# CONTROL_ROUTING_CROSSPOINTS.net
KiCad netlist of a schematic drawn in Altium Designer
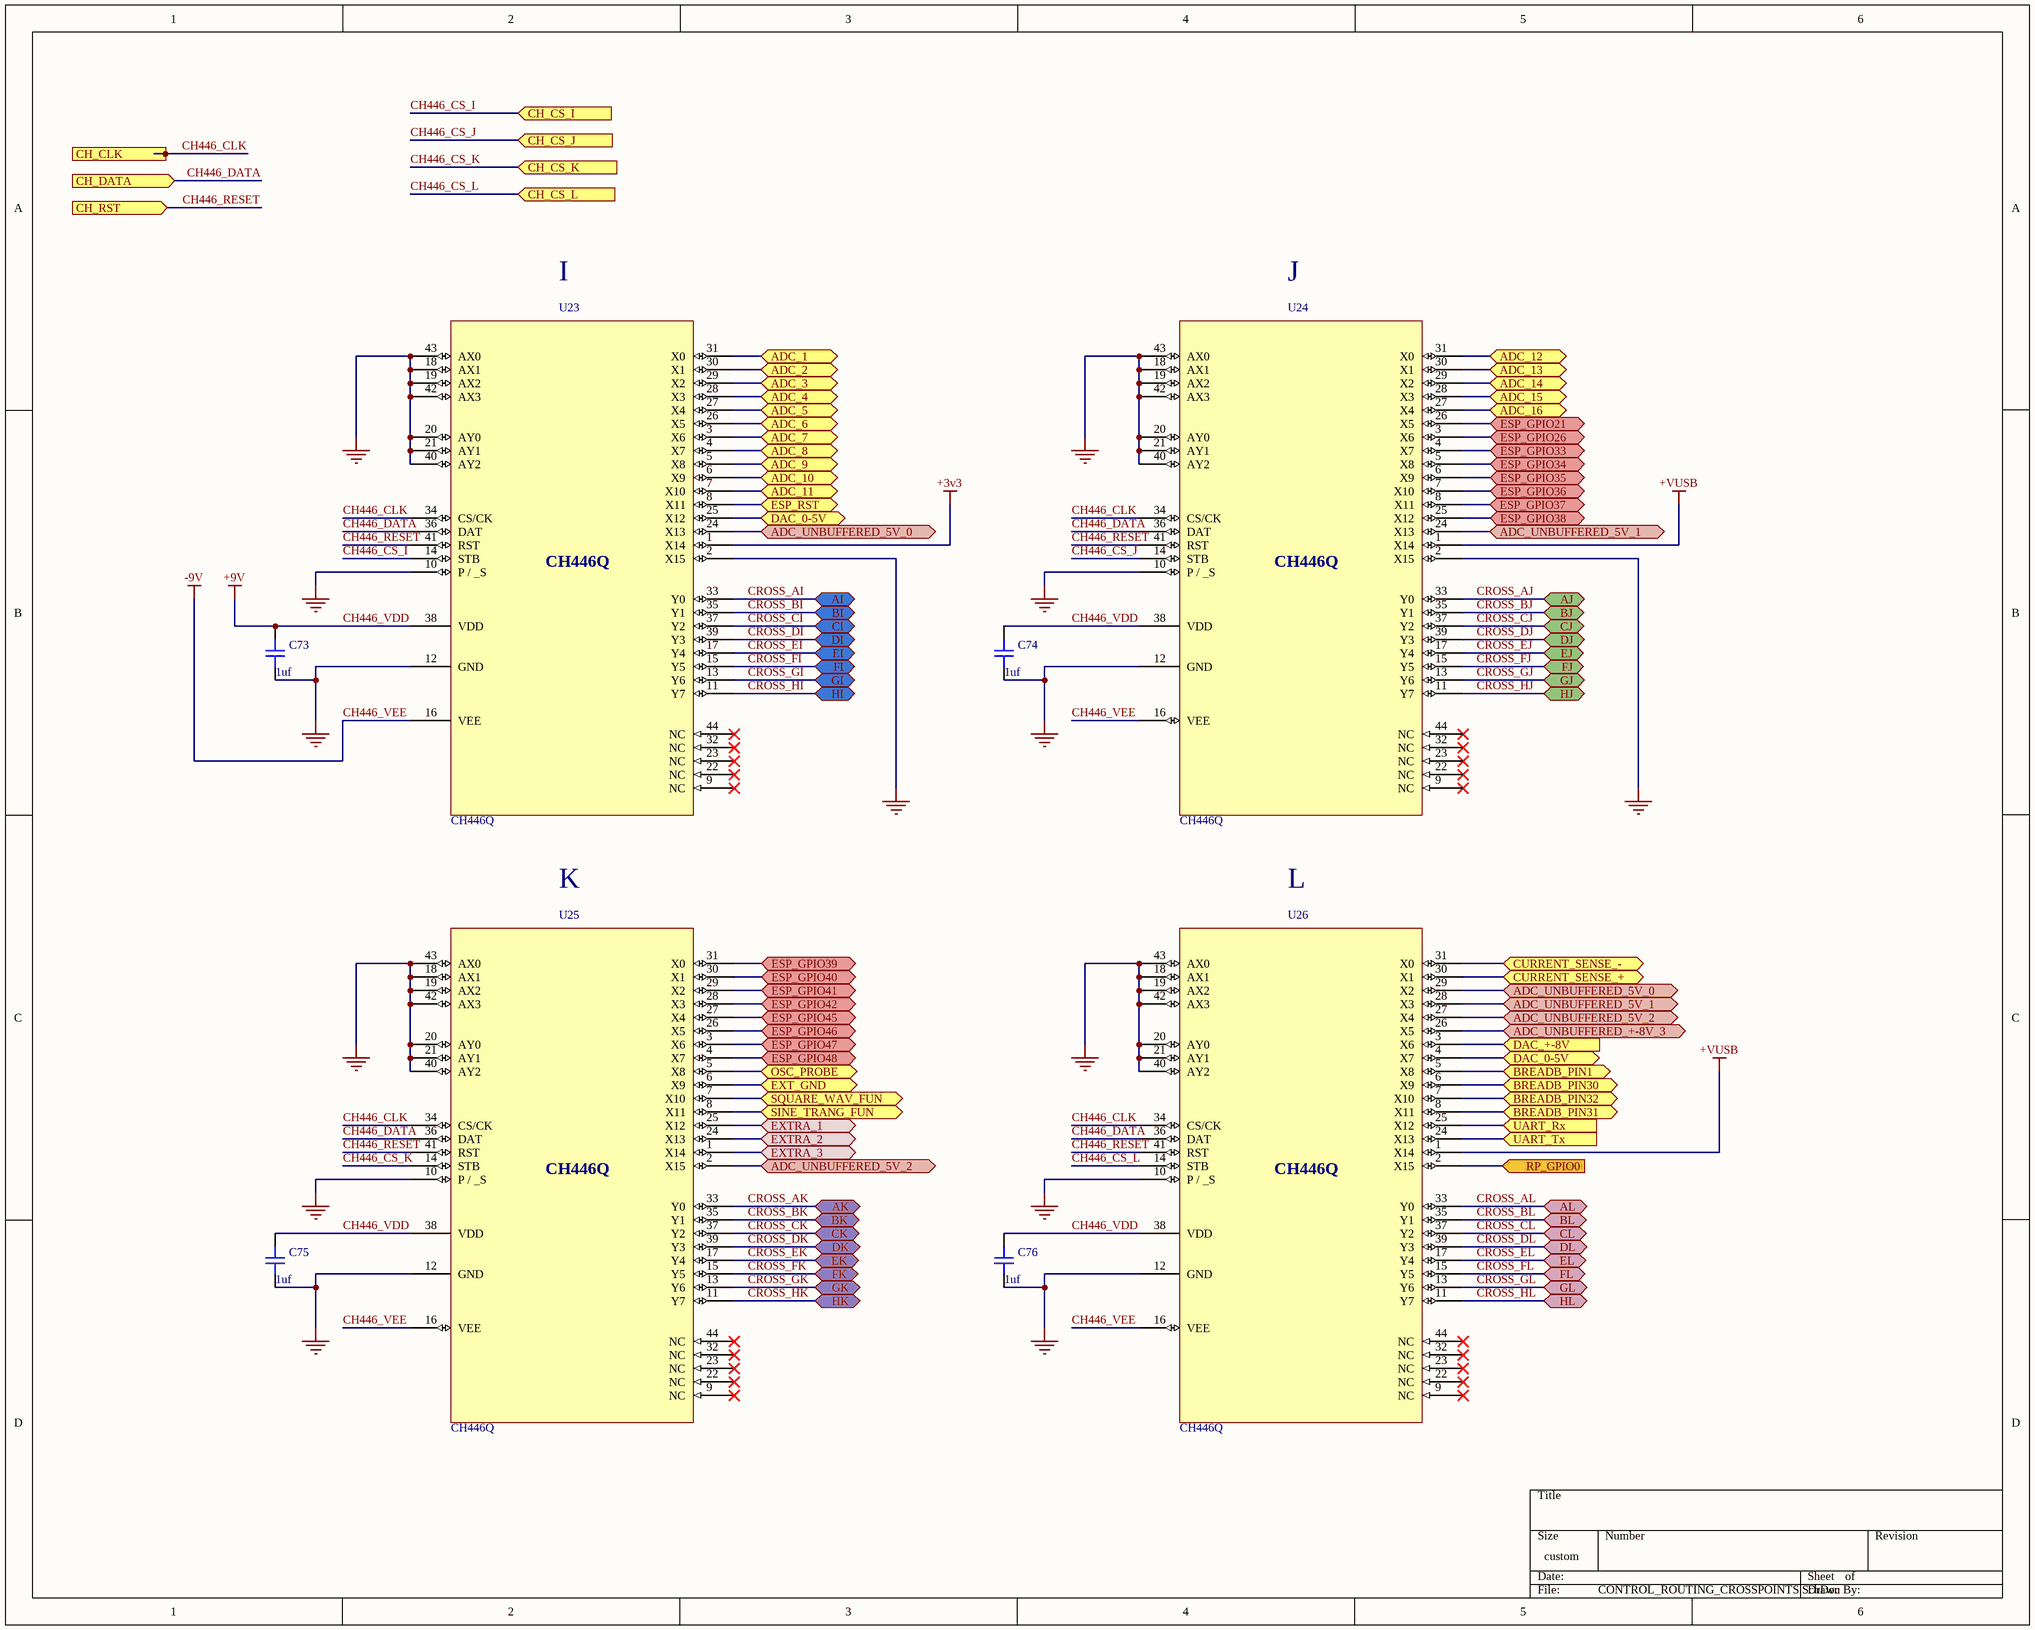
[diagram p0: CONTROL_ROUTING_CROSSPOINTS.SchDoc]

(export (version "E")
  (design (tool "Eeschema 10.0.6"))
  (components
    (comp (ref "C73")
      (value "1uf")
      (footprint "CAP_0603")
      (description "Capacitor SMD 0603")
      (libsource (lib "Schematic-Lib-PhilsLab") (part "CAP_0603"))
    )
    (comp (ref "C74")
      (value "1uf")
      (footprint "CAP_0603")
      (description "Capacitor SMD 0603")
      (libsource (lib "Schematic-Lib-PhilsLab") (part "CAP_0603"))
    )
    (comp (ref "C75")
      (value "1uf")
      (footprint "CAP_0603")
      (description "Capacitor SMD 0603")
      (libsource (lib "Schematic-Lib-PhilsLab") (part "CAP_0603"))
    )
    (comp (ref "C76")
      (value "1uf")
      (footprint "CAP_0603")
      (description "Capacitor SMD 0603")
      (libsource (lib "Schematic-Lib-PhilsLab") (part "CAP_0603"))
    )
    (comp (ref "U23") (value "CH446Q") (footprint "PG-LQFP-44") (libsource (lib "Schlib1") (part "CH446Q")))
    (comp (ref "U24") (value "CH446Q") (footprint "PG-LQFP-44") (libsource (lib "Schlib1") (part "CH446Q")))
    (comp (ref "U25") (value "CH446Q") (footprint "PG-LQFP-44") (libsource (lib "Schlib1") (part "CH446Q")))
    (comp (ref "U26") (value "CH446Q") (footprint "PG-LQFP-44") (libsource (lib "Schlib1") (part "CH446Q")))
  )
  (nets
    (net (code "1") (name "+3v3") (class "Default")
      (node (ref "U23") (pin "1") (pinfunction "X14_1") (pintype "bidirectional"))
    )
    (net (code "2") (name "+9V") (class "Default")
      (node (ref "C73") (pin "2") (pinfunction "2_2") (pintype "passive"))
      (node (ref "C74") (pin "2") (pinfunction "2_2") (pintype "passive"))
      (node (ref "C75") (pin "2") (pinfunction "2_2") (pintype "passive"))
      (node (ref "C76") (pin "2") (pinfunction "2_2") (pintype "passive"))
      (node (ref "U23") (pin "38") (pinfunction "VDD_38") (pintype "power_in"))
      (node (ref "U24") (pin "38") (pinfunction "VDD_38") (pintype "power_in"))
      (node (ref "U25") (pin "38") (pinfunction "VDD_38") (pintype "power_in"))
      (node (ref "U26") (pin "38") (pinfunction "VDD_38") (pintype "power_in"))
    )
    (net (code "3") (name "+VUSB") (class "Default")
      (node (ref "U24") (pin "1") (pinfunction "X14_1") (pintype "bidirectional"))
      (node (ref "U26") (pin "1") (pinfunction "X14_1") (pintype "bidirectional"))
    )
    (net (code "4") (name "-9V") (class "Default")
      (node (ref "U23") (pin "16") (pinfunction "VEE_16") (pintype "bidirectional"))
      (node (ref "U24") (pin "16") (pinfunction "VEE_16") (pintype "bidirectional"))
      (node (ref "U25") (pin "16") (pinfunction "VEE_16") (pintype "bidirectional"))
      (node (ref "U26") (pin "16") (pinfunction "VEE_16") (pintype "bidirectional"))
    )
    (net (code "5") (name "/ADC_1") (class "Default")
      (node (ref "U23") (pin "31") (pinfunction "X0_31") (pintype "bidirectional"))
    )
    (net (code "6") (name "/ADC_2") (class "Default")
      (node (ref "U23") (pin "30") (pinfunction "X1_30") (pintype "bidirectional"))
    )
    (net (code "7") (name "/ADC_3") (class "Default")
      (node (ref "U23") (pin "29") (pinfunction "X2_29") (pintype "bidirectional"))
    )
    (net (code "8") (name "/ADC_4") (class "Default")
      (node (ref "U23") (pin "28") (pinfunction "X3_28") (pintype "bidirectional"))
    )
    (net (code "9") (name "/ADC_5") (class "Default")
      (node (ref "U23") (pin "27") (pinfunction "X4_27") (pintype "bidirectional"))
    )
    (net (code "10") (name "/ADC_6") (class "Default")
      (node (ref "U23") (pin "26") (pinfunction "X5_26") (pintype "bidirectional"))
    )
    (net (code "11") (name "/ADC_7") (class "Default")
      (node (ref "U23") (pin "3") (pinfunction "X6_3") (pintype "bidirectional"))
    )
    (net (code "12") (name "/ADC_8") (class "Default")
      (node (ref "U23") (pin "4") (pinfunction "X7_4") (pintype "bidirectional"))
    )
    (net (code "13") (name "/ADC_9") (class "Default")
      (node (ref "U23") (pin "5") (pinfunction "X8_5") (pintype "bidirectional"))
    )
    (net (code "14") (name "/ADC_10") (class "Default")
      (node (ref "U23") (pin "6") (pinfunction "X9_6") (pintype "bidirectional"))
    )
    (net (code "15") (name "/ADC_11") (class "Default")
      (node (ref "U23") (pin "7") (pinfunction "X10_7") (pintype "bidirectional"))
    )
    (net (code "16") (name "/ADC_12") (class "Default")
      (node (ref "U24") (pin "31") (pinfunction "X0_31") (pintype "bidirectional"))
    )
    (net (code "17") (name "/ADC_13") (class "Default")
      (node (ref "U24") (pin "30") (pinfunction "X1_30") (pintype "bidirectional"))
    )
    (net (code "18") (name "/ADC_14") (class "Default")
      (node (ref "U24") (pin "29") (pinfunction "X2_29") (pintype "bidirectional"))
    )
    (net (code "19") (name "/ADC_15") (class "Default")
      (node (ref "U24") (pin "28") (pinfunction "X3_28") (pintype "bidirectional"))
    )
    (net (code "20") (name "/ADC_16") (class "Default")
      (node (ref "U24") (pin "27") (pinfunction "X4_27") (pintype "bidirectional"))
    )
    (net (code "21") (name "/ADC_UNBUFFERED_+-8V_3") (class "Default")
      (node (ref "U26") (pin "26") (pinfunction "X5_26") (pintype "bidirectional"))
    )
    (net (code "22") (name "/ADC_UNBUFFERED_5V_0") (class "Default")
      (node (ref "U23") (pin "24") (pinfunction "X13_24") (pintype "bidirectional"))
      (node (ref "U26") (pin "29") (pinfunction "X2_29") (pintype "bidirectional"))
    )
    (net (code "23") (name "/ADC_UNBUFFERED_5V_1") (class "Default")
      (node (ref "U24") (pin "24") (pinfunction "X13_24") (pintype "bidirectional"))
      (node (ref "U26") (pin "28") (pinfunction "X3_28") (pintype "bidirectional"))
    )
    (net (code "24") (name "/ADC_UNBUFFERED_5V_2") (class "Default")
      (node (ref "U25") (pin "2") (pinfunction "X15_2") (pintype "bidirectional"))
      (node (ref "U26") (pin "27") (pinfunction "X4_27") (pintype "bidirectional"))
    )
    (net (code "25") (name "/BREADB_PIN1") (class "Default")
      (node (ref "U26") (pin "5") (pinfunction "X8_5") (pintype "bidirectional"))
    )
    (net (code "26") (name "/BREADB_PIN30") (class "Default")
      (node (ref "U26") (pin "6") (pinfunction "X9_6") (pintype "bidirectional"))
    )
    (net (code "27") (name "/BREADB_PIN31") (class "Default")
      (node (ref "U26") (pin "8") (pinfunction "X11_8") (pintype "bidirectional"))
    )
    (net (code "28") (name "/BREADB_PIN32") (class "Default")
      (node (ref "U26") (pin "7") (pinfunction "X10_7") (pintype "bidirectional"))
    )
    (net (code "29") (name "/CH446_CLK") (class "Default")
      (node (ref "U23") (pin "34") (pinfunction "CS/CK_34") (pintype "bidirectional"))
      (node (ref "U24") (pin "34") (pinfunction "CS/CK_34") (pintype "bidirectional"))
      (node (ref "U25") (pin "34") (pinfunction "CS/CK_34") (pintype "bidirectional"))
      (node (ref "U26") (pin "34") (pinfunction "CS/CK_34") (pintype "bidirectional"))
    )
    (net (code "30") (name "/CH446_CS_I") (class "Default")
      (node (ref "U23") (pin "14") (pinfunction "STB_14") (pintype "bidirectional"))
    )
    (net (code "31") (name "/CH446_CS_J") (class "Default")
      (node (ref "U24") (pin "14") (pinfunction "STB_14") (pintype "bidirectional"))
    )
    (net (code "32") (name "/CH446_CS_K") (class "Default")
      (node (ref "U25") (pin "14") (pinfunction "STB_14") (pintype "bidirectional"))
    )
    (net (code "33") (name "/CH446_CS_L") (class "Default")
      (node (ref "U26") (pin "14") (pinfunction "STB_14") (pintype "bidirectional"))
    )
    (net (code "34") (name "/CH446_DATA") (class "Default")
      (node (ref "U23") (pin "36") (pinfunction "DAT_36") (pintype "bidirectional"))
      (node (ref "U24") (pin "36") (pinfunction "DAT_36") (pintype "bidirectional"))
      (node (ref "U25") (pin "36") (pinfunction "DAT_36") (pintype "bidirectional"))
      (node (ref "U26") (pin "36") (pinfunction "DAT_36") (pintype "bidirectional"))
    )
    (net (code "35") (name "/CH446_RESET") (class "Default")
      (node (ref "U23") (pin "41") (pinfunction "RST_41") (pintype "bidirectional"))
      (node (ref "U24") (pin "41") (pinfunction "RST_41") (pintype "bidirectional"))
      (node (ref "U25") (pin "41") (pinfunction "RST_41") (pintype "bidirectional"))
      (node (ref "U26") (pin "41") (pinfunction "RST_41") (pintype "bidirectional"))
    )
    (net (code "36") (name "/CROSS_AI") (class "Default")
      (node (ref "U23") (pin "33") (pinfunction "Y0_33") (pintype "bidirectional"))
    )
    (net (code "37") (name "/CROSS_AJ") (class "Default")
      (node (ref "U24") (pin "33") (pinfunction "Y0_33") (pintype "bidirectional"))
    )
    (net (code "38") (name "/CROSS_AK") (class "Default")
      (node (ref "U25") (pin "33") (pinfunction "Y0_33") (pintype "bidirectional"))
    )
    (net (code "39") (name "/CROSS_AL") (class "Default")
      (node (ref "U26") (pin "33") (pinfunction "Y0_33") (pintype "bidirectional"))
    )
    (net (code "40") (name "/CROSS_BI") (class "Default")
      (node (ref "U23") (pin "35") (pinfunction "Y1_35") (pintype "bidirectional"))
    )
    (net (code "41") (name "/CROSS_BJ") (class "Default")
      (node (ref "U24") (pin "35") (pinfunction "Y1_35") (pintype "bidirectional"))
    )
    (net (code "42") (name "/CROSS_BK") (class "Default")
      (node (ref "U25") (pin "35") (pinfunction "Y1_35") (pintype "bidirectional"))
    )
    (net (code "43") (name "/CROSS_BL") (class "Default")
      (node (ref "U26") (pin "35") (pinfunction "Y1_35") (pintype "bidirectional"))
    )
    (net (code "44") (name "/CROSS_CI") (class "Default")
      (node (ref "U23") (pin "37") (pinfunction "Y2_37") (pintype "bidirectional"))
    )
    (net (code "45") (name "/CROSS_CJ") (class "Default")
      (node (ref "U24") (pin "37") (pinfunction "Y2_37") (pintype "bidirectional"))
    )
    (net (code "46") (name "/CROSS_CK") (class "Default")
      (node (ref "U25") (pin "37") (pinfunction "Y2_37") (pintype "bidirectional"))
    )
    (net (code "47") (name "/CROSS_CL") (class "Default")
      (node (ref "U26") (pin "37") (pinfunction "Y2_37") (pintype "bidirectional"))
    )
    (net (code "48") (name "/CROSS_DI") (class "Default")
      (node (ref "U23") (pin "39") (pinfunction "Y3_39") (pintype "bidirectional"))
    )
    (net (code "49") (name "/CROSS_DJ") (class "Default")
      (node (ref "U24") (pin "39") (pinfunction "Y3_39") (pintype "bidirectional"))
    )
    (net (code "50") (name "/CROSS_DK") (class "Default")
      (node (ref "U25") (pin "39") (pinfunction "Y3_39") (pintype "bidirectional"))
    )
    (net (code "51") (name "/CROSS_DL") (class "Default")
      (node (ref "U26") (pin "39") (pinfunction "Y3_39") (pintype "bidirectional"))
    )
    (net (code "52") (name "/CROSS_EI") (class "Default")
      (node (ref "U23") (pin "17") (pinfunction "Y4_17") (pintype "bidirectional"))
    )
    (net (code "53") (name "/CROSS_EJ") (class "Default")
      (node (ref "U24") (pin "17") (pinfunction "Y4_17") (pintype "bidirectional"))
    )
    (net (code "54") (name "/CROSS_EK") (class "Default")
      (node (ref "U25") (pin "17") (pinfunction "Y4_17") (pintype "bidirectional"))
    )
    (net (code "55") (name "/CROSS_EL") (class "Default")
      (node (ref "U26") (pin "17") (pinfunction "Y4_17") (pintype "bidirectional"))
    )
    (net (code "56") (name "/CROSS_FI") (class "Default")
      (node (ref "U23") (pin "15") (pinfunction "Y5_15") (pintype "bidirectional"))
    )
    (net (code "57") (name "/CROSS_FJ") (class "Default")
      (node (ref "U24") (pin "15") (pinfunction "Y5_15") (pintype "bidirectional"))
    )
    (net (code "58") (name "/CROSS_FK") (class "Default")
      (node (ref "U25") (pin "15") (pinfunction "Y5_15") (pintype "bidirectional"))
    )
    (net (code "59") (name "/CROSS_FL") (class "Default")
      (node (ref "U26") (pin "15") (pinfunction "Y5_15") (pintype "bidirectional"))
    )
    (net (code "60") (name "/CROSS_GI") (class "Default")
      (node (ref "U23") (pin "13") (pinfunction "Y6_13") (pintype "bidirectional"))
    )
    (net (code "61") (name "/CROSS_GJ") (class "Default")
      (node (ref "U24") (pin "13") (pinfunction "Y6_13") (pintype "bidirectional"))
    )
    (net (code "62") (name "/CROSS_GK") (class "Default")
      (node (ref "U25") (pin "13") (pinfunction "Y6_13") (pintype "bidirectional"))
    )
    (net (code "63") (name "/CROSS_GL") (class "Default")
      (node (ref "U26") (pin "13") (pinfunction "Y6_13") (pintype "bidirectional"))
    )
    (net (code "64") (name "/CROSS_HI") (class "Default")
      (node (ref "U23") (pin "11") (pinfunction "Y7_11") (pintype "bidirectional"))
    )
    (net (code "65") (name "/CROSS_HJ") (class "Default")
      (node (ref "U24") (pin "11") (pinfunction "Y7_11") (pintype "bidirectional"))
    )
    (net (code "66") (name "/CROSS_HK") (class "Default")
      (node (ref "U25") (pin "11") (pinfunction "Y7_11") (pintype "bidirectional"))
    )
    (net (code "67") (name "/CROSS_HL") (class "Default")
      (node (ref "U26") (pin "11") (pinfunction "Y7_11") (pintype "bidirectional"))
    )
    (net (code "68") (name "/CURRENT_SENSE_+") (class "Default")
      (node (ref "U26") (pin "30") (pinfunction "X1_30") (pintype "bidirectional"))
    )
    (net (code "69") (name "/CURRENT_SENSE_-") (class "Default")
      (node (ref "U26") (pin "31") (pinfunction "X0_31") (pintype "bidirectional"))
    )
    (net (code "70") (name "/DAC_+-8V") (class "Default")
      (node (ref "U26") (pin "3") (pinfunction "X6_3") (pintype "bidirectional"))
    )
    (net (code "71") (name "/DAC_0-5V") (class "Default")
      (node (ref "U23") (pin "25") (pinfunction "X12_25") (pintype "bidirectional"))
      (node (ref "U26") (pin "4") (pinfunction "X7_4") (pintype "bidirectional"))
    )
    (net (code "72") (name "/ESP_GPIO21") (class "Default")
      (node (ref "U24") (pin "26") (pinfunction "X5_26") (pintype "bidirectional"))
    )
    (net (code "73") (name "/ESP_GPIO26") (class "Default")
      (node (ref "U24") (pin "3") (pinfunction "X6_3") (pintype "bidirectional"))
    )
    (net (code "74") (name "/ESP_GPIO33") (class "Default")
      (node (ref "U24") (pin "4") (pinfunction "X7_4") (pintype "bidirectional"))
    )
    (net (code "75") (name "/ESP_GPIO34") (class "Default")
      (node (ref "U24") (pin "5") (pinfunction "X8_5") (pintype "bidirectional"))
    )
    (net (code "76") (name "/ESP_GPIO35") (class "Default")
      (node (ref "U24") (pin "6") (pinfunction "X9_6") (pintype "bidirectional"))
    )
    (net (code "77") (name "/ESP_GPIO36") (class "Default")
      (node (ref "U24") (pin "7") (pinfunction "X10_7") (pintype "bidirectional"))
    )
    (net (code "78") (name "/ESP_GPIO37") (class "Default")
      (node (ref "U24") (pin "8") (pinfunction "X11_8") (pintype "bidirectional"))
    )
    (net (code "79") (name "/ESP_GPIO38") (class "Default")
      (node (ref "U24") (pin "25") (pinfunction "X12_25") (pintype "bidirectional"))
    )
    (net (code "80") (name "/ESP_GPIO39") (class "Default")
      (node (ref "U25") (pin "31") (pinfunction "X0_31") (pintype "bidirectional"))
    )
    (net (code "81") (name "/ESP_GPIO40") (class "Default")
      (node (ref "U25") (pin "30") (pinfunction "X1_30") (pintype "bidirectional"))
    )
    (net (code "82") (name "/ESP_GPIO41") (class "Default")
      (node (ref "U25") (pin "29") (pinfunction "X2_29") (pintype "bidirectional"))
    )
    (net (code "83") (name "/ESP_GPIO42") (class "Default")
      (node (ref "U25") (pin "28") (pinfunction "X3_28") (pintype "bidirectional"))
    )
    (net (code "84") (name "/ESP_GPIO45") (class "Default")
      (node (ref "U25") (pin "27") (pinfunction "X4_27") (pintype "bidirectional"))
    )
    (net (code "85") (name "/ESP_GPIO46") (class "Default")
      (node (ref "U25") (pin "26") (pinfunction "X5_26") (pintype "bidirectional"))
    )
    (net (code "86") (name "/ESP_GPIO47") (class "Default")
      (node (ref "U25") (pin "3") (pinfunction "X6_3") (pintype "bidirectional"))
    )
    (net (code "87") (name "/ESP_GPIO48") (class "Default")
      (node (ref "U25") (pin "4") (pinfunction "X7_4") (pintype "bidirectional"))
    )
    (net (code "88") (name "/ESP_RST") (class "Default")
      (node (ref "U23") (pin "8") (pinfunction "X11_8") (pintype "bidirectional"))
    )
    (net (code "89") (name "/EXTRA_1") (class "Default")
      (node (ref "U25") (pin "25") (pinfunction "X12_25") (pintype "bidirectional"))
    )
    (net (code "90") (name "/EXTRA_2") (class "Default")
      (node (ref "U25") (pin "24") (pinfunction "X13_24") (pintype "bidirectional"))
    )
    (net (code "91") (name "/EXTRA_3") (class "Default")
      (node (ref "U25") (pin "1") (pinfunction "X14_1") (pintype "bidirectional"))
    )
    (net (code "92") (name "/EXT_GND") (class "Default")
      (node (ref "U25") (pin "6") (pinfunction "X9_6") (pintype "bidirectional"))
    )
    (net (code "93") (name "/OSC_PROBE") (class "Default")
      (node (ref "U25") (pin "5") (pinfunction "X8_5") (pintype "bidirectional"))
    )
    (net (code "94") (name "/RP_GPIO0") (class "Default")
      (node (ref "U26") (pin "2") (pinfunction "X15_2") (pintype "bidirectional"))
    )
    (net (code "95") (name "/SINE_TRANG_FUN") (class "Default")
      (node (ref "U25") (pin "8") (pinfunction "X11_8") (pintype "bidirectional"))
    )
    (net (code "96") (name "/SQUARE_WAV_FUN") (class "Default")
      (node (ref "U25") (pin "7") (pinfunction "X10_7") (pintype "bidirectional"))
    )
    (net (code "97") (name "/UART_Rx") (class "Default")
      (node (ref "U26") (pin "25") (pinfunction "X12_25") (pintype "bidirectional"))
    )
    (net (code "98") (name "/UART_Tx") (class "Default")
      (node (ref "U26") (pin "24") (pinfunction "X13_24") (pintype "bidirectional"))
    )
    (net (code "99") (name "GND") (class "Default")
      (node (ref "C73") (pin "1") (pinfunction "1_1") (pintype "passive"))
      (node (ref "C74") (pin "1") (pinfunction "1_1") (pintype "passive"))
      (node (ref "C75") (pin "1") (pinfunction "1_1") (pintype "passive"))
      (node (ref "C76") (pin "1") (pinfunction "1_1") (pintype "passive"))
      (node (ref "U23") (pin "10") (pinfunction "P_/__S_10") (pintype "bidirectional"))
      (node (ref "U23") (pin "12") (pinfunction "GND_12") (pintype "power_in"))
      (node (ref "U23") (pin "18") (pinfunction "AX1_18") (pintype "bidirectional"))
      (node (ref "U23") (pin "19") (pinfunction "AX2_19") (pintype "bidirectional"))
      (node (ref "U23") (pin "2") (pinfunction "X15_2") (pintype "bidirectional"))
      (node (ref "U23") (pin "20") (pinfunction "AY0_20") (pintype "bidirectional"))
      (node (ref "U23") (pin "21") (pinfunction "AY1_21") (pintype "bidirectional"))
      (node (ref "U23") (pin "40") (pinfunction "AY2_40") (pintype "bidirectional"))
      (node (ref "U23") (pin "42") (pinfunction "AX3_42") (pintype "bidirectional"))
      (node (ref "U23") (pin "43") (pinfunction "AX0_43") (pintype "bidirectional"))
      (node (ref "U24") (pin "10") (pinfunction "P_/__S_10") (pintype "bidirectional"))
      (node (ref "U24") (pin "12") (pinfunction "GND_12") (pintype "power_in"))
      (node (ref "U24") (pin "18") (pinfunction "AX1_18") (pintype "bidirectional"))
      (node (ref "U24") (pin "19") (pinfunction "AX2_19") (pintype "bidirectional"))
      (node (ref "U24") (pin "2") (pinfunction "X15_2") (pintype "bidirectional"))
      (node (ref "U24") (pin "20") (pinfunction "AY0_20") (pintype "bidirectional"))
      (node (ref "U24") (pin "21") (pinfunction "AY1_21") (pintype "bidirectional"))
      (node (ref "U24") (pin "40") (pinfunction "AY2_40") (pintype "bidirectional"))
      (node (ref "U24") (pin "42") (pinfunction "AX3_42") (pintype "bidirectional"))
      (node (ref "U24") (pin "43") (pinfunction "AX0_43") (pintype "bidirectional"))
      (node (ref "U25") (pin "10") (pinfunction "P_/__S_10") (pintype "bidirectional"))
      (node (ref "U25") (pin "12") (pinfunction "GND_12") (pintype "power_in"))
      (node (ref "U25") (pin "18") (pinfunction "AX1_18") (pintype "bidirectional"))
      (node (ref "U25") (pin "19") (pinfunction "AX2_19") (pintype "bidirectional"))
      (node (ref "U25") (pin "20") (pinfunction "AY0_20") (pintype "bidirectional"))
      (node (ref "U25") (pin "21") (pinfunction "AY1_21") (pintype "bidirectional"))
      (node (ref "U25") (pin "40") (pinfunction "AY2_40") (pintype "bidirectional"))
      (node (ref "U25") (pin "42") (pinfunction "AX3_42") (pintype "bidirectional"))
      (node (ref "U25") (pin "43") (pinfunction "AX0_43") (pintype "bidirectional"))
      (node (ref "U26") (pin "10") (pinfunction "P_/__S_10") (pintype "bidirectional"))
      (node (ref "U26") (pin "12") (pinfunction "GND_12") (pintype "power_in"))
      (node (ref "U26") (pin "18") (pinfunction "AX1_18") (pintype "bidirectional"))
      (node (ref "U26") (pin "19") (pinfunction "AX2_19") (pintype "bidirectional"))
      (node (ref "U26") (pin "20") (pinfunction "AY0_20") (pintype "bidirectional"))
      (node (ref "U26") (pin "21") (pinfunction "AY1_21") (pintype "bidirectional"))
      (node (ref "U26") (pin "40") (pinfunction "AY2_40") (pintype "bidirectional"))
      (node (ref "U26") (pin "42") (pinfunction "AX3_42") (pintype "bidirectional"))
      (node (ref "U26") (pin "43") (pinfunction "AX0_43") (pintype "bidirectional"))
    )
    (net (code "100") (name "unconnected-(U23-NC-Pad9)") (class "Default")
      (node (ref "U23") (pin "9") (pinfunction "NC_9") (pintype "input+no_connect"))
    )
    (net (code "101") (name "unconnected-(U23-NC-Pad22)") (class "Default")
      (node (ref "U23") (pin "22") (pinfunction "NC_22") (pintype "input+no_connect"))
    )
    (net (code "102") (name "unconnected-(U23-NC-Pad23)") (class "Default")
      (node (ref "U23") (pin "23") (pinfunction "NC_23") (pintype "input+no_connect"))
    )
    (net (code "103") (name "unconnected-(U23-NC-Pad32)") (class "Default")
      (node (ref "U23") (pin "32") (pinfunction "NC_32") (pintype "input+no_connect"))
    )
    (net (code "104") (name "unconnected-(U23-NC-Pad44)") (class "Default")
      (node (ref "U23") (pin "44") (pinfunction "NC_44") (pintype "input+no_connect"))
    )
    (net (code "105") (name "unconnected-(U24-NC-Pad9)") (class "Default")
      (node (ref "U24") (pin "9") (pinfunction "NC_9") (pintype "input+no_connect"))
    )
    (net (code "106") (name "unconnected-(U24-NC-Pad22)") (class "Default")
      (node (ref "U24") (pin "22") (pinfunction "NC_22") (pintype "input+no_connect"))
    )
    (net (code "107") (name "unconnected-(U24-NC-Pad23)") (class "Default")
      (node (ref "U24") (pin "23") (pinfunction "NC_23") (pintype "input+no_connect"))
    )
    (net (code "108") (name "unconnected-(U24-NC-Pad32)") (class "Default")
      (node (ref "U24") (pin "32") (pinfunction "NC_32") (pintype "input+no_connect"))
    )
    (net (code "109") (name "unconnected-(U24-NC-Pad44)") (class "Default")
      (node (ref "U24") (pin "44") (pinfunction "NC_44") (pintype "input+no_connect"))
    )
    (net (code "110") (name "unconnected-(U25-NC-Pad9)") (class "Default")
      (node (ref "U25") (pin "9") (pinfunction "NC_9") (pintype "input+no_connect"))
    )
    (net (code "111") (name "unconnected-(U25-NC-Pad22)") (class "Default")
      (node (ref "U25") (pin "22") (pinfunction "NC_22") (pintype "input+no_connect"))
    )
    (net (code "112") (name "unconnected-(U25-NC-Pad23)") (class "Default")
      (node (ref "U25") (pin "23") (pinfunction "NC_23") (pintype "input+no_connect"))
    )
    (net (code "113") (name "unconnected-(U25-NC-Pad32)") (class "Default")
      (node (ref "U25") (pin "32") (pinfunction "NC_32") (pintype "input+no_connect"))
    )
    (net (code "114") (name "unconnected-(U25-NC-Pad44)") (class "Default")
      (node (ref "U25") (pin "44") (pinfunction "NC_44") (pintype "input+no_connect"))
    )
    (net (code "115") (name "unconnected-(U26-NC-Pad9)") (class "Default")
      (node (ref "U26") (pin "9") (pinfunction "NC_9") (pintype "input+no_connect"))
    )
    (net (code "116") (name "unconnected-(U26-NC-Pad22)") (class "Default")
      (node (ref "U26") (pin "22") (pinfunction "NC_22") (pintype "input+no_connect"))
    )
    (net (code "117") (name "unconnected-(U26-NC-Pad23)") (class "Default")
      (node (ref "U26") (pin "23") (pinfunction "NC_23") (pintype "input+no_connect"))
    )
    (net (code "118") (name "unconnected-(U26-NC-Pad32)") (class "Default")
      (node (ref "U26") (pin "32") (pinfunction "NC_32") (pintype "input+no_connect"))
    )
    (net (code "119") (name "unconnected-(U26-NC-Pad44)") (class "Default")
      (node (ref "U26") (pin "44") (pinfunction "NC_44") (pintype "input+no_connect"))
    )
  )
)
